# mboard_mem.net
KiCad netlist of a schematic drawn in Altium Designer
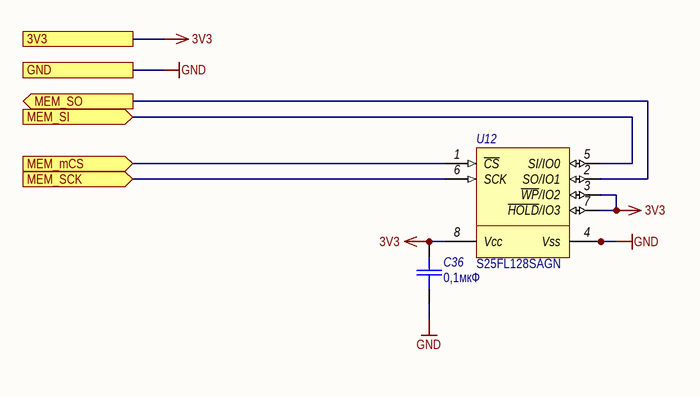
[diagram p0: mboard_mem.SchDoc]

(export (version "E")
  (design (tool "Eeschema 10.0.6"))
  (components
    (comp (ref "C36")
      (value "0,1мкФ")
      (footprint "SMD_C0402")
      (description "Capacitor")
      (fields (field (name "Comment") "K10-79"))
      (libsource (lib "Passive") (part "Capacitor"))
    )
    (comp (ref "U12")
      (value "S25FL128SAGN")
      (footprint "WSON-8_6x8")
      (description "Programmable NOR flash memory")
      (fields (field (name "НАИМЕНОВАНИЕ") "S25FL128SAGN"))
      (libsource (lib "Memory") (part "S25FL128SAGN"))
    )
  )
  (nets
    (net (code "1") (name "/MEM_SCK") (class "Default")
      (node (ref "U12") (pin "6") (pinfunction "SCK_6") (pintype "input"))
    )
    (net (code "2") (name "/MEM_SI") (class "Default")
      (node (ref "U12") (pin "5") (pinfunction "SI/IO0_5") (pintype "bidirectional"))
    )
    (net (code "3") (name "/MEM_SO") (class "Default")
      (node (ref "U12") (pin "2") (pinfunction "SO/IO1_2") (pintype "bidirectional"))
    )
    (net (code "4") (name "/MEM_mCS") (class "Default")
      (node (ref "U12") (pin "1") (pinfunction "~{CS}_1") (pintype "input"))
    )
    (net (code "5") (name "3V3") (class "Default")
      (node (ref "C36") (pin "1") (pinfunction "1_1") (pintype "passive"))
      (node (ref "U12") (pin "3") (pinfunction "~{WP}/IO2_3") (pintype "bidirectional"))
      (node (ref "U12") (pin "7") (pinfunction "~{HOLD}/IO3_7") (pintype "bidirectional"))
      (node (ref "U12") (pin "8") (pinfunction "Vcc_8") (pintype "power_in"))
    )
    (net (code "6") (name "GND") (class "Default")
      (node (ref "C36") (pin "2") (pinfunction "2_2") (pintype "passive"))
      (node (ref "U12") (pin "4") (pinfunction "Vss_4") (pintype "power_in"))
      (node (ref "U12") (pin "9") (pinfunction "TP_9") (pintype "power_in"))
    )
  )
)
